# V-00321-00.net
KiCad netlist of a schematic drawn in EAGLE
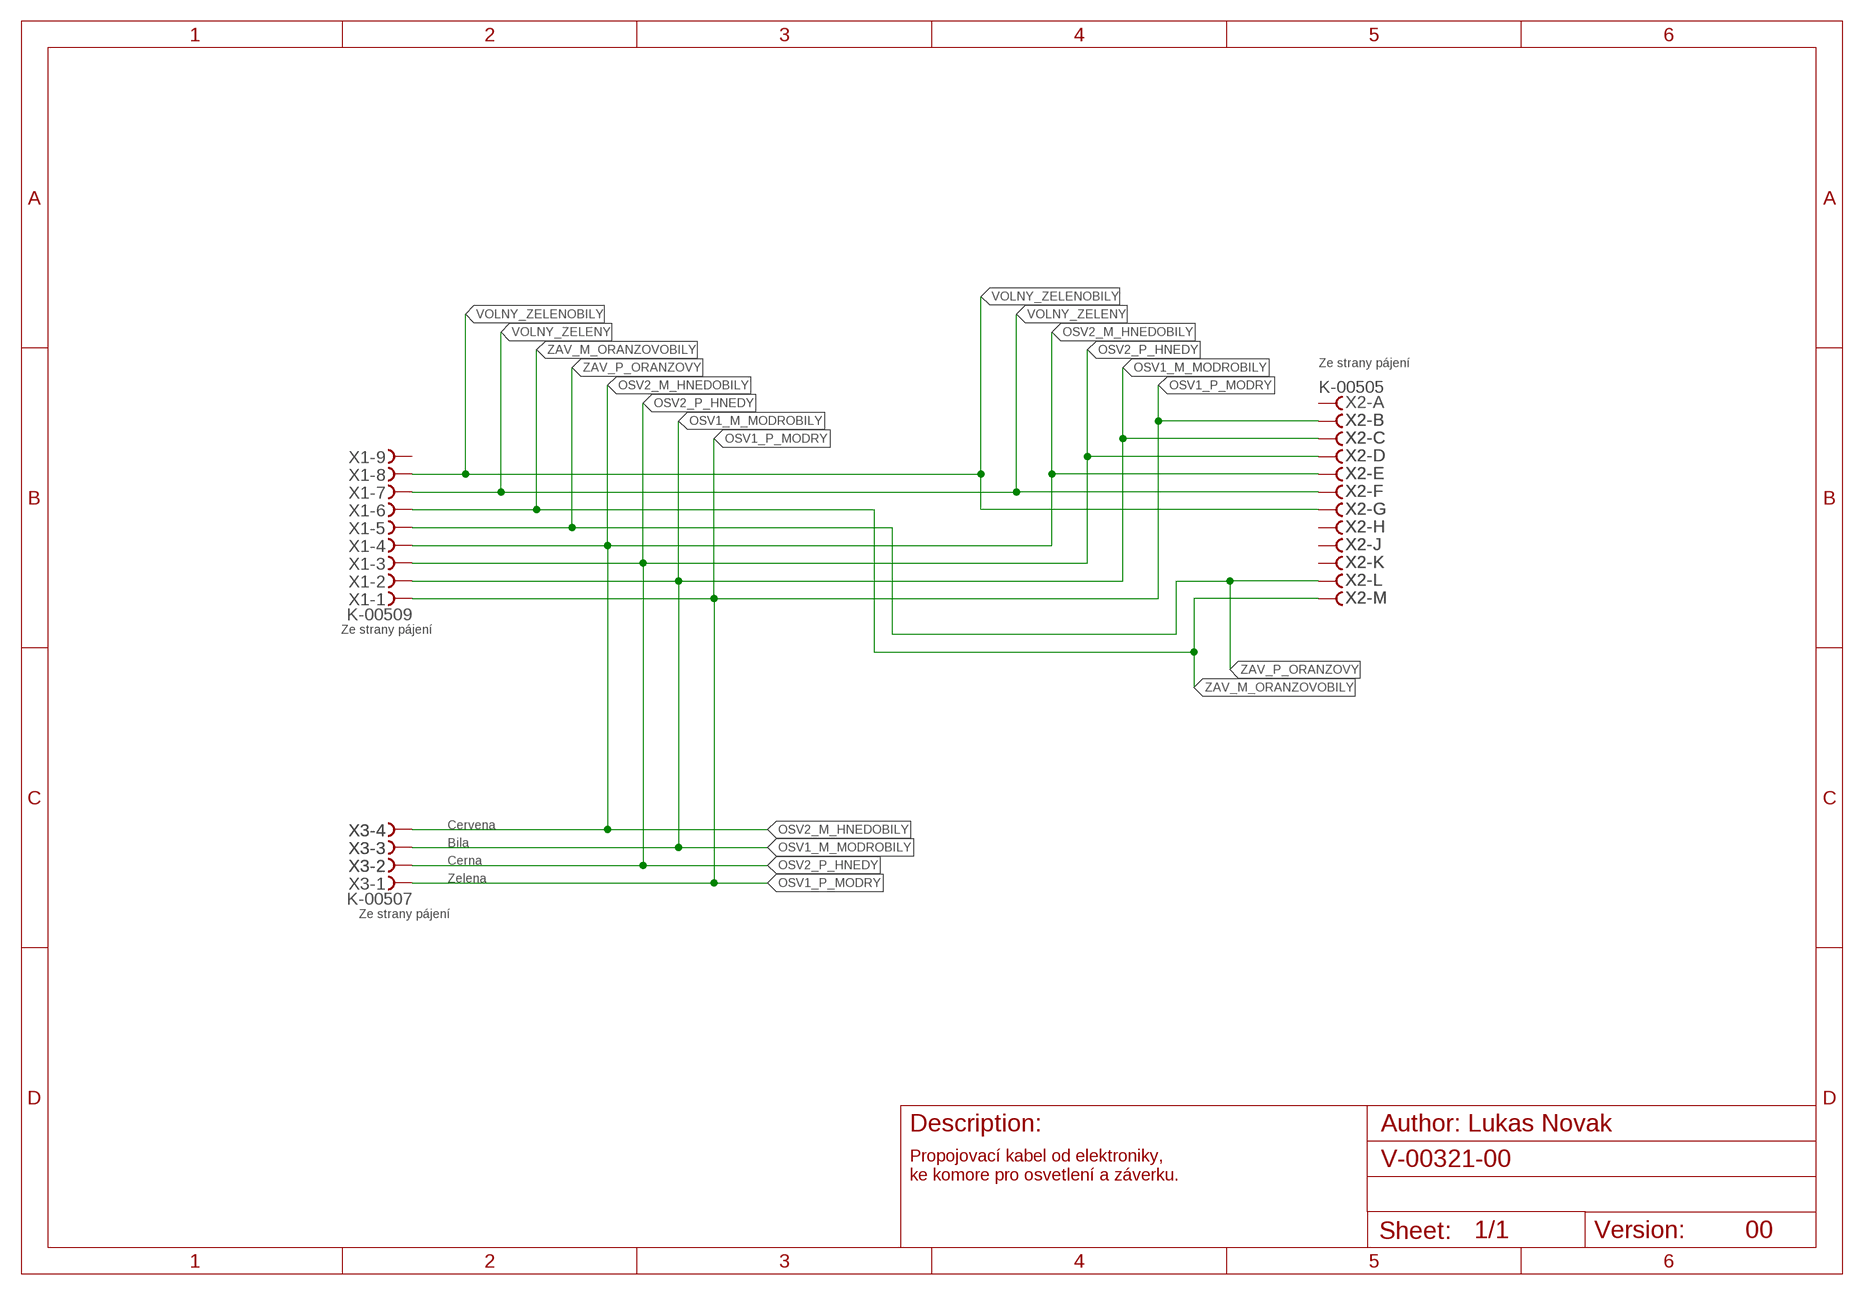
[diagram p0: schematic, sheet 1]

(export (version "E")
  (design (tool "Eeschema 10.0.6"))
  (components
    (comp (ref "X1")
      (value "K-00509")
      (footprint "eagle-import:H2M09ST")
      (libsource (lib "eagle-import") (part "D-SUB9-H2M09ST"))
    )
    (comp (ref "X2")
      (value "K-00505")
      (footprint "eagle-import:LU12MP")
      (libsource (lib "eagle-import") (part "LU12MP"))
    )
    (comp (ref "X3")
      (value "K-00507")
      (footprint "eagle-import:LE4MP")
      (libsource (lib "eagle-import") (part "LE4MP"))
    )
  )
  (nets
    (net (code "1") (name "OSV1_M_MODROBILY") (class "Default")
      (node (ref "X1") (pin "2") (pinfunction "F_2") (pintype "passive"))
      (node (ref "X2") (pin "C") (pinfunction "F_C") (pintype "passive"))
      (node (ref "X3") (pin "3") (pinfunction "F_3") (pintype "passive"))
    )
    (net (code "2") (name "OSV1_P_MODRY") (class "Default")
      (node (ref "X1") (pin "1") (pinfunction "F_1") (pintype "passive"))
      (node (ref "X2") (pin "B") (pinfunction "F_B") (pintype "passive"))
      (node (ref "X3") (pin "1") (pinfunction "F_1") (pintype "passive"))
    )
    (net (code "3") (name "OSV2_M_HNEDOBILY") (class "Default")
      (node (ref "X1") (pin "4") (pinfunction "F_4") (pintype "passive"))
      (node (ref "X2") (pin "E") (pinfunction "F_E") (pintype "passive"))
      (node (ref "X3") (pin "4") (pinfunction "F_4") (pintype "passive"))
    )
    (net (code "4") (name "OSV2_P_HNEDY") (class "Default")
      (node (ref "X1") (pin "3") (pinfunction "F_3") (pintype "passive"))
      (node (ref "X2") (pin "D") (pinfunction "F_D") (pintype "passive"))
      (node (ref "X3") (pin "2") (pinfunction "F_2") (pintype "passive"))
    )
    (net (code "5") (name "VOLNY_ZELENOBILY") (class "Default")
      (node (ref "X1") (pin "8") (pinfunction "F_8") (pintype "passive"))
      (node (ref "X2") (pin "G") (pinfunction "F_G") (pintype "passive"))
    )
    (net (code "6") (name "VOLNY_ZELENY") (class "Default")
      (node (ref "X1") (pin "7") (pinfunction "F_7") (pintype "passive"))
      (node (ref "X2") (pin "F") (pinfunction "F_F") (pintype "passive"))
    )
    (net (code "7") (name "ZAV_M_ORANZOVOBILY") (class "Default")
      (node (ref "X1") (pin "6") (pinfunction "F_6") (pintype "passive"))
      (node (ref "X2") (pin "M") (pinfunction "F_M") (pintype "passive"))
    )
    (net (code "8") (name "ZAV_P_ORANZOVY") (class "Default")
      (node (ref "X1") (pin "5") (pinfunction "F_5") (pintype "passive"))
      (node (ref "X2") (pin "L") (pinfunction "F_L") (pintype "passive"))
    )
    (net (code "9") (name "unconnected-(X1I-F-Pad9)") (class "Default")
      (node (ref "X1") (pin "9") (pinfunction "F_9") (pintype "passive"))
    )
    (net (code "10") (name "unconnected-(X2A-F-PadA)") (class "Default")
      (node (ref "X2") (pin "A") (pinfunction "F_A") (pintype "passive"))
    )
    (net (code "11") (name "unconnected-(X2H-F-PadH)") (class "Default")
      (node (ref "X2") (pin "H") (pinfunction "F_H") (pintype "passive"))
    )
    (net (code "12") (name "unconnected-(X2I-F-PadJ)") (class "Default")
      (node (ref "X2") (pin "J") (pinfunction "F_J") (pintype "passive"))
    )
    (net (code "13") (name "unconnected-(X2J-F-PadK)") (class "Default")
      (node (ref "X2") (pin "K") (pinfunction "F_K") (pintype "passive"))
    )
  )
)
